# Atmega_128_Dev_Board.net
KiCad netlist of a schematic drawn in EAGLE
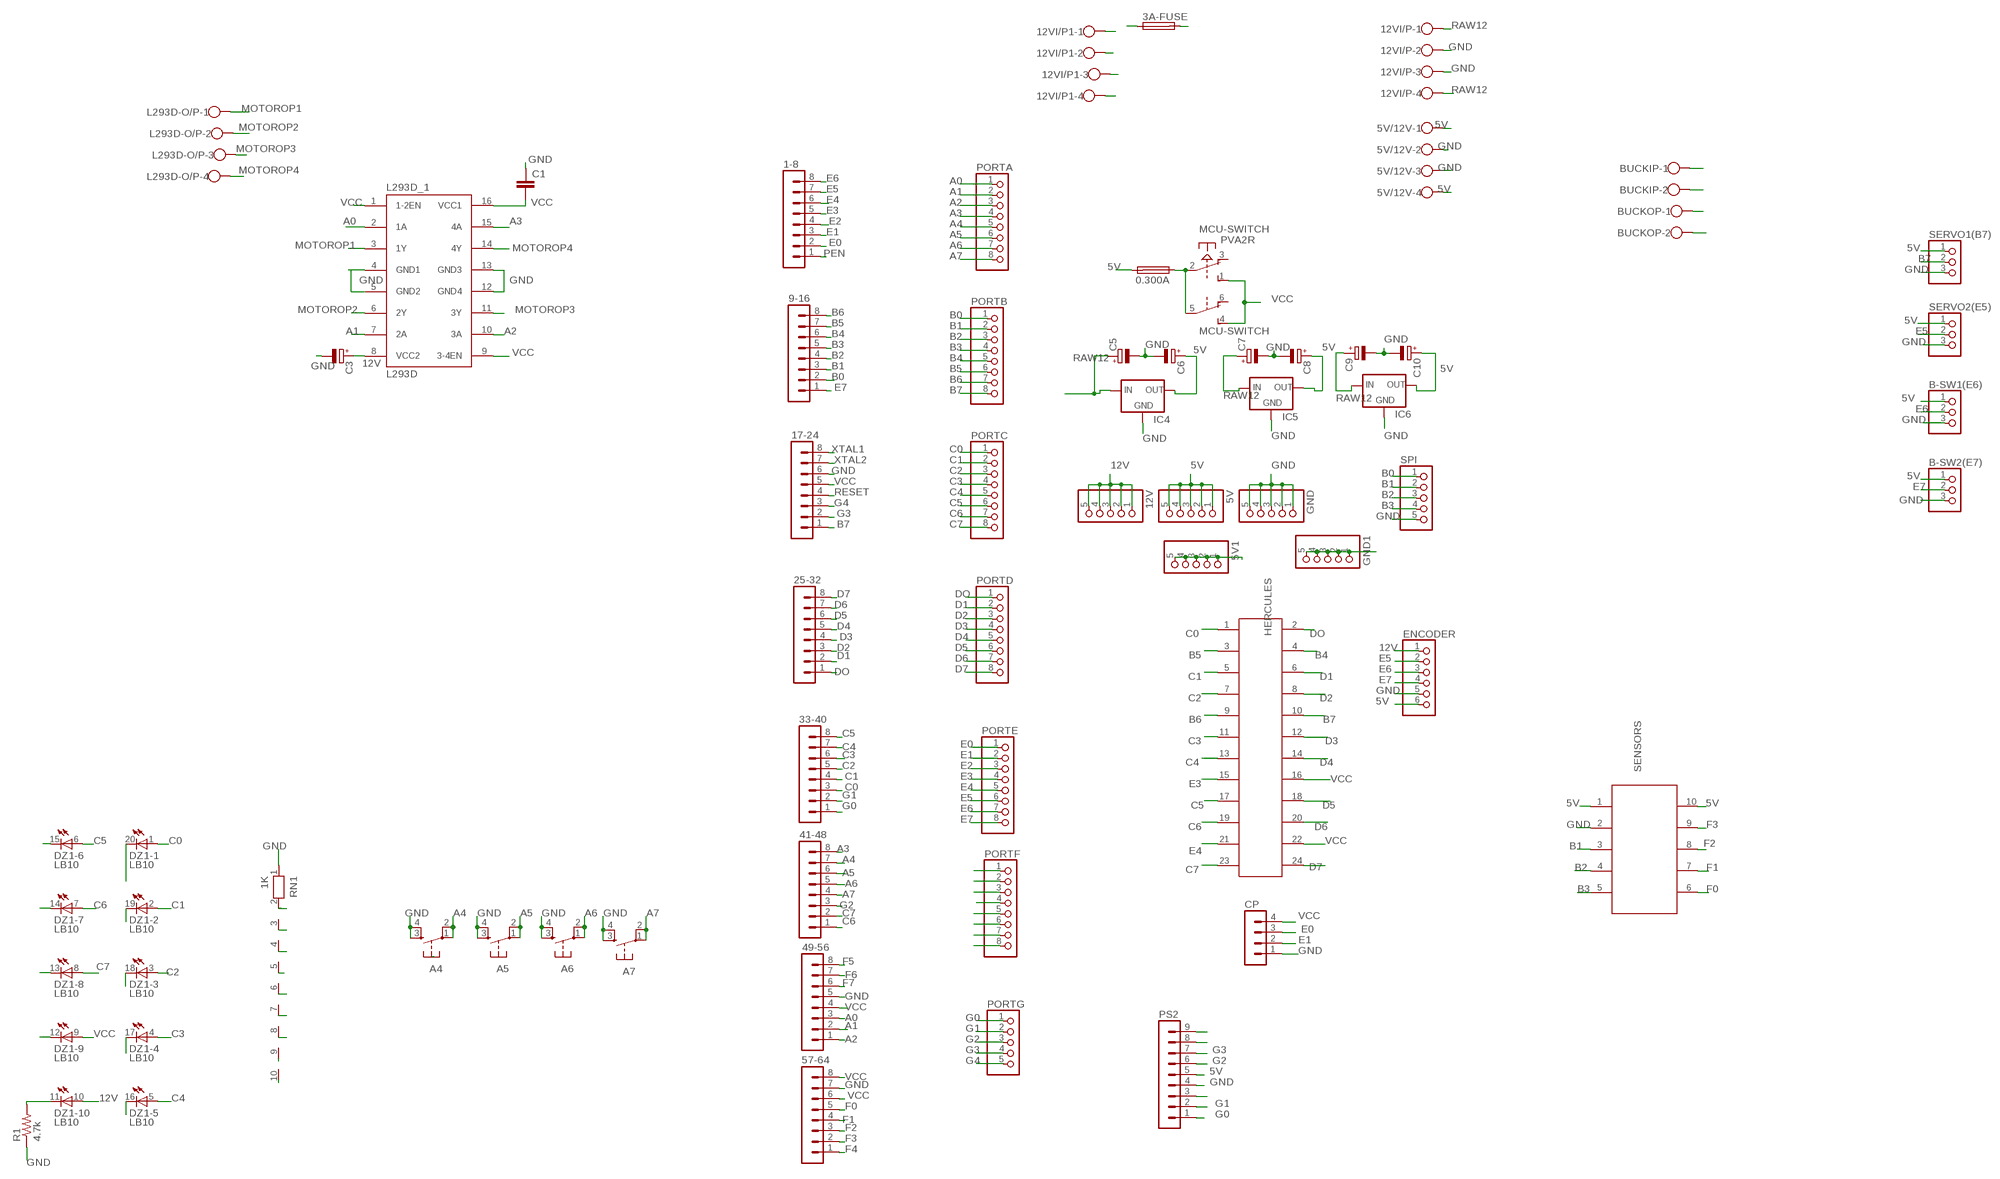
[diagram p0: schematic, sheet 1]

(export (version "E")
  (design (tool "Eeschema 10.0.6"))
  (components
    (comp (ref "0.300A")
      (value "SH25")
      (footprint "eagle-import:SH25")
      (fields (field (name "MF") "SCHURTER") (field (name "MPN") "0031.8211"))
      (libsource (lib "eagle-import") (part "SH25"))
    )
    (comp (ref "1-8")
      (value "MA08-1")
      (footprint "eagle-import:MA08-1")
      (libsource (lib "eagle-import") (part "MA08-1"))
    )
    (comp (ref "3A-FUSE")
      (value "SH25")
      (footprint "eagle-import:SH25")
      (fields (field (name "MF") "SCHURTER") (field (name "MPN") "0031.8211"))
      (libsource (lib "eagle-import") (part "SH25"))
    )
    (comp (ref "5V")
      (value "PINHD-1X5")
      (footprint "eagle-import:1X05")
      (libsource (lib "eagle-import") (part "PINHD-1X5"))
    )
    (comp (ref "5V/12V")
      (value "W237-4")
      (footprint "eagle-import:W237-4")
      (libsource (lib "eagle-import") (part "W237-4"))
    )
    (comp (ref "5V1")
      (value "PINHD-1X5")
      (footprint "eagle-import:1X05")
      (libsource (lib "eagle-import") (part "PINHD-1X5"))
    )
    (comp (ref "9-16")
      (value "MA08-1")
      (footprint "eagle-import:MA08-1")
      (libsource (lib "eagle-import") (part "MA08-1"))
    )
    (comp (ref "12V")
      (value "PINHD-1X5")
      (footprint "eagle-import:1X05")
      (libsource (lib "eagle-import") (part "PINHD-1X5"))
    )
    (comp (ref "12VI/P")
      (value "W237-4")
      (footprint "eagle-import:W237-4")
      (libsource (lib "eagle-import") (part "W237-4"))
    )
    (comp (ref "12VI/P1")
      (value "W237-4")
      (footprint "eagle-import:W237-4")
      (libsource (lib "eagle-import") (part "W237-4"))
    )
    (comp (ref "17-24")
      (value "MA08-1")
      (footprint "eagle-import:MA08-1")
      (libsource (lib "eagle-import") (part "MA08-1"))
    )
    (comp (ref "25-32")
      (value "MA08-1")
      (footprint "eagle-import:MA08-1")
      (libsource (lib "eagle-import") (part "MA08-1"))
    )
    (comp (ref "33-40")
      (value "MA08-1")
      (footprint "eagle-import:MA08-1")
      (libsource (lib "eagle-import") (part "MA08-1"))
    )
    (comp (ref "41-48")
      (value "MA08-1")
      (footprint "eagle-import:MA08-1")
      (libsource (lib "eagle-import") (part "MA08-1"))
    )
    (comp (ref "49-56")
      (value "MA08-1")
      (footprint "eagle-import:MA08-1")
      (libsource (lib "eagle-import") (part "MA08-1"))
    )
    (comp (ref "57-64")
      (value "MA08-1")
      (footprint "eagle-import:MA08-1")
      (libsource (lib "eagle-import") (part "MA08-1"))
    )
    (comp (ref "A4")
      (value "DTS-6")
      (footprint "eagle-import:DTS-6")
      (libsource (lib "eagle-import") (part "DTS-6"))
    )
    (comp (ref "A5")
      (value "DTS-6")
      (footprint "eagle-import:DTS-6")
      (libsource (lib "eagle-import") (part "DTS-6"))
    )
    (comp (ref "A6")
      (value "DTS-6")
      (footprint "eagle-import:DTS-6")
      (libsource (lib "eagle-import") (part "DTS-6"))
    )
    (comp (ref "A7")
      (value "DTS-6")
      (footprint "eagle-import:DTS-6")
      (libsource (lib "eagle-import") (part "DTS-6"))
    )
    (comp (ref "B-SW1(E6)")
      (value "PINHD-1X3")
      (footprint "eagle-import:1X03")
      (libsource (lib "eagle-import") (part "PINHD-1X3"))
    )
    (comp (ref "B-SW2(E7)")
      (value "PINHD-1X3")
      (footprint "eagle-import:1X03")
      (libsource (lib "eagle-import") (part "PINHD-1X3"))
    )
    (comp (ref "BUCKIP")
      (value "W237-102")
      (footprint "eagle-import:W237-102")
      (fields (field (name "MPN") "237-102"))
      (libsource (lib "eagle-import") (part "W237-102"))
    )
    (comp (ref "BUCKOP")
      (value "W237-102")
      (footprint "eagle-import:W237-102")
      (fields (field (name "MPN") "237-102"))
      (libsource (lib "eagle-import") (part "W237-102"))
    )
    (comp (ref "C1")
      (value "C5/2.5")
      (footprint "eagle-import:C5B2.5")
      (libsource (lib "eagle-import") (part "C5/2.5"))
    )
    (comp (ref "C3")
      (value "CPOL-EUE2.5-5")
      (footprint "eagle-import:E2,5-5")
      (libsource (lib "eagle-import") (part "CPOL-EUE2.5-5"))
    )
    (comp (ref "C5")
      (value "CPOL-EUE2.5-5")
      (footprint "eagle-import:E2,5-5")
      (libsource (lib "eagle-import") (part "CPOL-EUE2.5-5"))
    )
    (comp (ref "C6")
      (value "CPOL-EUE2.5-5")
      (footprint "eagle-import:E2,5-5")
      (libsource (lib "eagle-import") (part "CPOL-EUE2.5-5"))
    )
    (comp (ref "C7")
      (value "CPOL-EUE2.5-5")
      (footprint "eagle-import:E2,5-5")
      (libsource (lib "eagle-import") (part "CPOL-EUE2.5-5"))
    )
    (comp (ref "C8")
      (value "CPOL-EUE2.5-5")
      (footprint "eagle-import:E2,5-5")
      (libsource (lib "eagle-import") (part "CPOL-EUE2.5-5"))
    )
    (comp (ref "C9")
      (value "CPOL-EUE2.5-5")
      (footprint "eagle-import:E2,5-5")
      (libsource (lib "eagle-import") (part "CPOL-EUE2.5-5"))
    )
    (comp (ref "C10")
      (value "CPOL-EUE2.5-5")
      (footprint "eagle-import:E2,5-5")
      (libsource (lib "eagle-import") (part "CPOL-EUE2.5-5"))
    )
    (comp (ref "CP")
      (value "MA04-1")
      (footprint "eagle-import:MA04-1")
      (libsource (lib "eagle-import") (part "MA04-1"))
    )
    (comp (ref "DZ1")
      (value "LB10")
      (footprint "eagle-import:LB10")
      (libsource (lib "eagle-import") (part "LB10"))
    )
    (comp (ref "ENCODER")
      (value "PINHD-1X6")
      (footprint "eagle-import:1X06")
      (libsource (lib "eagle-import") (part "PINHD-1X6"))
    )
    (comp (ref "GND")
      (value "PINHD-1X5")
      (footprint "eagle-import:1X05")
      (libsource (lib "eagle-import") (part "PINHD-1X5"))
    )
    (comp (ref "GND1")
      (value "PINHD-1X5")
      (footprint "eagle-import:1X05")
      (libsource (lib "eagle-import") (part "PINHD-1X5"))
    )
    (comp (ref "HERCULES")
      (value "61202421621")
      (footprint "eagle-import:61202421621")
      (libsource (lib "eagle-import") (part "61202421621"))
    )
    (comp (ref "IC4")
      (value "78XXS")
      (footprint "eagle-import:78XXS")
      (libsource (lib "eagle-import") (part "78XXS"))
    )
    (comp (ref "IC5")
      (value "78XXS")
      (footprint "eagle-import:78XXS")
      (libsource (lib "eagle-import") (part "78XXS"))
    )
    (comp (ref "IC6")
      (value "78XXS")
      (footprint "eagle-import:78XXS")
      (libsource (lib "eagle-import") (part "78XXS"))
    )
    (comp (ref "L293D-O/P")
      (value "W237-4")
      (footprint "eagle-import:W237-4")
      (libsource (lib "eagle-import") (part "W237-4"))
    )
    (comp (ref "L293D_1")
      (value "L293D")
      (footprint "eagle-import:DIL16")
      (libsource (lib "eagle-import") (part "L293D"))
    )
    (comp (ref "MCU-SWITCH")
      (value "PVA2R")
      (footprint "eagle-import:PVA2R")
      (libsource (lib "eagle-import") (part "PVA2R"))
    )
    (comp (ref "PORTA")
      (value "PINHD-1X8")
      (footprint "eagle-import:1X08")
      (libsource (lib "eagle-import") (part "PINHD-1X8"))
    )
    (comp (ref "PORTB")
      (value "PINHD-1X8")
      (footprint "eagle-import:1X08")
      (libsource (lib "eagle-import") (part "PINHD-1X8"))
    )
    (comp (ref "PORTC")
      (value "PINHD-1X8")
      (footprint "eagle-import:1X08")
      (libsource (lib "eagle-import") (part "PINHD-1X8"))
    )
    (comp (ref "PORTD")
      (value "PINHD-1X8")
      (footprint "eagle-import:1X08")
      (libsource (lib "eagle-import") (part "PINHD-1X8"))
    )
    (comp (ref "PORTE")
      (value "PINHD-1X8")
      (footprint "eagle-import:1X08")
      (libsource (lib "eagle-import") (part "PINHD-1X8"))
    )
    (comp (ref "PORTF")
      (value "PINHD-1X8")
      (footprint "eagle-import:1X08")
      (libsource (lib "eagle-import") (part "PINHD-1X8"))
    )
    (comp (ref "PORTG")
      (value "PINHD-1X5")
      (footprint "eagle-import:1X05")
      (libsource (lib "eagle-import") (part "PINHD-1X5"))
    )
    (comp (ref "PS2")
      (value "MA09-1")
      (footprint "eagle-import:MA09-1")
      (libsource (lib "eagle-import") (part "MA09-1"))
    )
    (comp (ref "R1")
      (value "4.7k")
      (footprint "eagle-import:0204_7")
      (libsource (lib "eagle-import") (part "R-US_0204/7"))
    )
    (comp (ref "RN1")
      (value "1K")
      (footprint "eagle-import:RN-10")
      (libsource (lib "eagle-import") (part "RN09"))
    )
    (comp (ref "SENSORS")
      (value "66101021622")
      (footprint "eagle-import:66101021622")
      (libsource (lib "eagle-import") (part "66101021622"))
    )
    (comp (ref "SERVO1(B7)")
      (value "PINHD-1X3")
      (footprint "eagle-import:1X03")
      (libsource (lib "eagle-import") (part "PINHD-1X3"))
    )
    (comp (ref "SERVO2(E5)")
      (value "PINHD-1X3")
      (footprint "eagle-import:1X03")
      (libsource (lib "eagle-import") (part "PINHD-1X3"))
    )
    (comp (ref "SPI")
      (value "PINHD-1X5")
      (footprint "eagle-import:1X05")
      (libsource (lib "eagle-import") (part "PINHD-1X5"))
    )
  )
  (nets
    (net (code "1") (name "/2") (class "Default")
      (node (ref "DZ1") (pin "12") (pinfunction "C_12") (pintype "passive"))
      (node (ref "RN1") (pin "2") (pinfunction "2_2") (pintype "passive"))
    )
    (net (code "2") (name "/3") (class "Default")
      (node (ref "DZ1") (pin "13") (pinfunction "C_13") (pintype "passive"))
      (node (ref "RN1") (pin "3") (pinfunction "3_3") (pintype "passive"))
    )
    (net (code "3") (name "/4") (class "Default")
      (node (ref "DZ1") (pin "14") (pinfunction "C_14") (pintype "passive"))
      (node (ref "RN1") (pin "4") (pinfunction "4_4") (pintype "passive"))
    )
    (net (code "4") (name "/5") (class "Default")
      (node (ref "DZ1") (pin "15") (pinfunction "C_15") (pintype "passive"))
      (node (ref "RN1") (pin "5") (pinfunction "5_5") (pintype "passive"))
    )
    (net (code "5") (name "/5V") (class "Default")
      (node (ref "0.300A") (pin "2") (pinfunction "2_2") (pintype "passive"))
      (node (ref "5V") (pin "1") (pinfunction "1_1") (pintype "passive"))
      (node (ref "5V") (pin "2") (pinfunction "2_2") (pintype "passive"))
      (node (ref "5V") (pin "3") (pinfunction "3_3") (pintype "passive"))
      (node (ref "5V") (pin "4") (pinfunction "4_4") (pintype "passive"))
      (node (ref "5V") (pin "5") (pinfunction "5_5") (pintype "passive"))
      (node (ref "5V/12V") (pin "1") (pinfunction "KL_1") (pintype "passive"))
      (node (ref "5V/12V") (pin "4") (pinfunction "KL_4") (pintype "passive"))
      (node (ref "5V1") (pin "1") (pinfunction "1_1") (pintype "passive"))
      (node (ref "5V1") (pin "2") (pinfunction "2_2") (pintype "passive"))
      (node (ref "5V1") (pin "3") (pinfunction "3_3") (pintype "passive"))
      (node (ref "5V1") (pin "4") (pinfunction "4_4") (pintype "passive"))
      (node (ref "5V1") (pin "5") (pinfunction "5_5") (pintype "passive"))
      (node (ref "B-SW1(E6)") (pin "1") (pinfunction "1_1") (pintype "passive"))
      (node (ref "B-SW2(E7)") (pin "1") (pinfunction "1_1") (pintype "passive"))
      (node (ref "BUCKOP") (pin "2") (pinfunction "KL_2") (pintype "passive"))
      (node (ref "C10") (pin "+") (pinfunction "+_+") (pintype "passive"))
      (node (ref "C6") (pin "+") (pinfunction "+_+") (pintype "passive"))
      (node (ref "C8") (pin "+") (pinfunction "+_+") (pintype "passive"))
      (node (ref "ENCODER") (pin "6") (pinfunction "6_6") (pintype "passive"))
      (node (ref "IC4") (pin "OUT") (pinfunction "OUT_OUT") (pintype "passive"))
      (node (ref "IC5") (pin "OUT") (pinfunction "OUT_OUT") (pintype "passive"))
      (node (ref "IC6") (pin "OUT") (pinfunction "OUT_OUT") (pintype "passive"))
      (node (ref "PS2") (pin "5") (pinfunction "5_5") (pintype "passive"))
      (node (ref "SENSORS") (pin "1") (pinfunction "6_1") (pintype "bidirectional"))
      (node (ref "SENSORS") (pin "10") (pinfunction "1_10") (pintype "bidirectional"))
      (node (ref "SERVO1(B7)") (pin "1") (pinfunction "1_1") (pintype "passive"))
      (node (ref "SERVO2(E5)") (pin "1") (pinfunction "1_1") (pintype "passive"))
    )
    (net (code "6") (name "/6") (class "Default")
      (node (ref "DZ1") (pin "16") (pinfunction "C_16") (pintype "passive"))
      (node (ref "RN1") (pin "6") (pinfunction "6_6") (pintype "passive"))
    )
    (net (code "7") (name "/7") (class "Default")
      (node (ref "DZ1") (pin "17") (pinfunction "C_17") (pintype "passive"))
      (node (ref "RN1") (pin "7") (pinfunction "7_7") (pintype "passive"))
    )
    (net (code "8") (name "/8") (class "Default")
      (node (ref "DZ1") (pin "18") (pinfunction "C_18") (pintype "passive"))
      (node (ref "RN1") (pin "8") (pinfunction "8_8") (pintype "passive"))
    )
    (net (code "9") (name "/9") (class "Default")
      (node (ref "DZ1") (pin "19") (pinfunction "C_19") (pintype "passive"))
      (node (ref "RN1") (pin "9") (pinfunction "9_9") (pintype "passive"))
    )
    (net (code "10") (name "/10") (class "Default")
      (node (ref "DZ1") (pin "20") (pinfunction "C_20") (pintype "passive"))
      (node (ref "RN1") (pin "10") (pinfunction "10_10") (pintype "passive"))
    )
    (net (code "11") (name "/12V") (class "Default")
      (node (ref "12V") (pin "1") (pinfunction "1_1") (pintype "passive"))
      (node (ref "12V") (pin "2") (pinfunction "2_2") (pintype "passive"))
      (node (ref "12V") (pin "3") (pinfunction "3_3") (pintype "passive"))
      (node (ref "12V") (pin "4") (pinfunction "4_4") (pintype "passive"))
      (node (ref "12V") (pin "5") (pinfunction "5_5") (pintype "passive"))
      (node (ref "3A-FUSE") (pin "2") (pinfunction "2_2") (pintype "passive"))
      (node (ref "C3") (pin "+") (pinfunction "+_+") (pintype "passive"))
      (node (ref "DZ1") (pin "10") (pinfunction "A_10") (pintype "passive"))
      (node (ref "ENCODER") (pin "1") (pinfunction "1_1") (pintype "passive"))
      (node (ref "L293D_1") (pin "8") (pinfunction "VCC2_8") (pintype "power_in"))
    )
    (net (code "12") (name "/A0") (class "Default")
      (node (ref "49-56") (pin "3") (pinfunction "3_3") (pintype "passive"))
      (node (ref "L293D_1") (pin "2") (pinfunction "1A_2") (pintype "input"))
      (node (ref "PORTA") (pin "1") (pinfunction "1_1") (pintype "passive"))
    )
    (net (code "13") (name "/A1") (class "Default")
      (node (ref "49-56") (pin "2") (pinfunction "2_2") (pintype "passive"))
      (node (ref "L293D_1") (pin "7") (pinfunction "2A_7") (pintype "input"))
      (node (ref "PORTA") (pin "2") (pinfunction "2_2") (pintype "passive"))
    )
    (net (code "14") (name "/A2") (class "Default")
      (node (ref "49-56") (pin "1") (pinfunction "1_1") (pintype "passive"))
      (node (ref "L293D_1") (pin "10") (pinfunction "3A_10") (pintype "input"))
      (node (ref "PORTA") (pin "3") (pinfunction "3_3") (pintype "passive"))
    )
    (net (code "15") (name "/A3") (class "Default")
      (node (ref "41-48") (pin "8") (pinfunction "8_8") (pintype "passive"))
      (node (ref "L293D_1") (pin "15") (pinfunction "4A_15") (pintype "input"))
      (node (ref "PORTA") (pin "4") (pinfunction "4_4") (pintype "passive"))
    )
    (net (code "16") (name "/A4") (class "Default")
      (node (ref "41-48") (pin "7") (pinfunction "7_7") (pintype "passive"))
      (node (ref "A4") (pin "1") (pinfunction "1_1") (pintype "passive"))
      (node (ref "A4") (pin "2") (pinfunction "2_2") (pintype "passive"))
      (node (ref "PORTA") (pin "5") (pinfunction "5_5") (pintype "passive"))
    )
    (net (code "17") (name "/A5") (class "Default")
      (node (ref "41-48") (pin "6") (pinfunction "6_6") (pintype "passive"))
      (node (ref "A5") (pin "1") (pinfunction "1_1") (pintype "passive"))
      (node (ref "A5") (pin "2") (pinfunction "2_2") (pintype "passive"))
      (node (ref "PORTA") (pin "6") (pinfunction "6_6") (pintype "passive"))
    )
    (net (code "18") (name "/A6") (class "Default")
      (node (ref "41-48") (pin "5") (pinfunction "5_5") (pintype "passive"))
      (node (ref "A6") (pin "1") (pinfunction "1_1") (pintype "passive"))
      (node (ref "A6") (pin "2") (pinfunction "2_2") (pintype "passive"))
      (node (ref "PORTA") (pin "7") (pinfunction "7_7") (pintype "passive"))
    )
    (net (code "19") (name "/A7") (class "Default")
      (node (ref "41-48") (pin "4") (pinfunction "4_4") (pintype "passive"))
      (node (ref "A7") (pin "1") (pinfunction "1_1") (pintype "passive"))
      (node (ref "A7") (pin "2") (pinfunction "2_2") (pintype "passive"))
      (node (ref "PORTA") (pin "8") (pinfunction "8_8") (pintype "passive"))
    )
    (net (code "20") (name "/B0") (class "Default")
      (node (ref "9-16") (pin "2") (pinfunction "2_2") (pintype "passive"))
      (node (ref "PORTB") (pin "1") (pinfunction "1_1") (pintype "passive"))
      (node (ref "SPI") (pin "1") (pinfunction "1_1") (pintype "passive"))
    )
    (net (code "21") (name "/B1") (class "Default")
      (node (ref "9-16") (pin "3") (pinfunction "3_3") (pintype "passive"))
      (node (ref "PORTB") (pin "2") (pinfunction "2_2") (pintype "passive"))
      (node (ref "SENSORS") (pin "3") (pinfunction "8_3") (pintype "bidirectional"))
      (node (ref "SPI") (pin "2") (pinfunction "2_2") (pintype "passive"))
    )
    (net (code "22") (name "/B2") (class "Default")
      (node (ref "9-16") (pin "4") (pinfunction "4_4") (pintype "passive"))
      (node (ref "PORTB") (pin "3") (pinfunction "3_3") (pintype "passive"))
      (node (ref "SENSORS") (pin "4") (pinfunction "9_4") (pintype "bidirectional"))
      (node (ref "SPI") (pin "3") (pinfunction "3_3") (pintype "passive"))
    )
    (net (code "23") (name "/B3") (class "Default")
      (node (ref "9-16") (pin "5") (pinfunction "5_5") (pintype "passive"))
      (node (ref "PORTB") (pin "4") (pinfunction "4_4") (pintype "passive"))
      (node (ref "SENSORS") (pin "5") (pinfunction "10_5") (pintype "bidirectional"))
      (node (ref "SPI") (pin "4") (pinfunction "4_4") (pintype "passive"))
    )
    (net (code "24") (name "/B4") (class "Default")
      (node (ref "9-16") (pin "6") (pinfunction "6_6") (pintype "passive"))
      (node (ref "HERCULES") (pin "4") (pinfunction "4_4") (pintype "passive"))
      (node (ref "PORTB") (pin "5") (pinfunction "5_5") (pintype "passive"))
    )
    (net (code "25") (name "/B5") (class "Default")
      (node (ref "9-16") (pin "7") (pinfunction "7_7") (pintype "passive"))
      (node (ref "HERCULES") (pin "3") (pinfunction "3_3") (pintype "passive"))
      (node (ref "PORTB") (pin "6") (pinfunction "6_6") (pintype "passive"))
    )
    (net (code "26") (name "/B6") (class "Default")
      (node (ref "9-16") (pin "8") (pinfunction "8_8") (pintype "passive"))
      (node (ref "HERCULES") (pin "9") (pinfunction "9_9") (pintype "passive"))
      (node (ref "PORTB") (pin "7") (pinfunction "7_7") (pintype "passive"))
    )
    (net (code "27") (name "/B7") (class "Default")
      (node (ref "17-24") (pin "1") (pinfunction "1_1") (pintype "passive"))
      (node (ref "HERCULES") (pin "10") (pinfunction "10_10") (pintype "passive"))
      (node (ref "PORTB") (pin "8") (pinfunction "8_8") (pintype "passive"))
      (node (ref "SERVO1(B7)") (pin "2") (pinfunction "2_2") (pintype "passive"))
    )
    (net (code "28") (name "/C0") (class "Default")
      (node (ref "33-40") (pin "3") (pinfunction "3_3") (pintype "passive"))
      (node (ref "DZ1") (pin "1") (pinfunction "A_1") (pintype "passive"))
      (node (ref "HERCULES") (pin "1") (pinfunction "1_1") (pintype "passive"))
      (node (ref "PORTC") (pin "1") (pinfunction "1_1") (pintype "passive"))
    )
    (net (code "29") (name "/C1") (class "Default")
      (node (ref "33-40") (pin "4") (pinfunction "4_4") (pintype "passive"))
      (node (ref "DZ1") (pin "2") (pinfunction "A_2") (pintype "passive"))
      (node (ref "HERCULES") (pin "5") (pinfunction "5_5") (pintype "passive"))
      (node (ref "PORTC") (pin "2") (pinfunction "2_2") (pintype "passive"))
    )
    (net (code "30") (name "/C2") (class "Default")
      (node (ref "33-40") (pin "5") (pinfunction "5_5") (pintype "passive"))
      (node (ref "DZ1") (pin "3") (pinfunction "A_3") (pintype "passive"))
      (node (ref "HERCULES") (pin "7") (pinfunction "7_7") (pintype "passive"))
      (node (ref "PORTC") (pin "3") (pinfunction "3_3") (pintype "passive"))
    )
    (net (code "31") (name "/C3") (class "Default")
      (node (ref "33-40") (pin "6") (pinfunction "6_6") (pintype "passive"))
      (node (ref "DZ1") (pin "4") (pinfunction "A_4") (pintype "passive"))
      (node (ref "HERCULES") (pin "11") (pinfunction "11_11") (pintype "passive"))
      (node (ref "PORTC") (pin "4") (pinfunction "4_4") (pintype "passive"))
    )
    (net (code "32") (name "/C4") (class "Default")
      (node (ref "33-40") (pin "7") (pinfunction "7_7") (pintype "passive"))
      (node (ref "DZ1") (pin "5") (pinfunction "A_5") (pintype "passive"))
      (node (ref "HERCULES") (pin "13") (pinfunction "13_13") (pintype "passive"))
      (node (ref "PORTC") (pin "5") (pinfunction "5_5") (pintype "passive"))
    )
    (net (code "33") (name "/C5") (class "Default")
      (node (ref "33-40") (pin "8") (pinfunction "8_8") (pintype "passive"))
      (node (ref "DZ1") (pin "6") (pinfunction "A_6") (pintype "passive"))
      (node (ref "HERCULES") (pin "17") (pinfunction "17_17") (pintype "passive"))
      (node (ref "PORTC") (pin "6") (pinfunction "6_6") (pintype "passive"))
    )
    (net (code "34") (name "/C6") (class "Default")
      (node (ref "41-48") (pin "1") (pinfunction "1_1") (pintype "passive"))
      (node (ref "DZ1") (pin "7") (pinfunction "A_7") (pintype "passive"))
      (node (ref "HERCULES") (pin "19") (pinfunction "19_19") (pintype "passive"))
      (node (ref "PORTC") (pin "7") (pinfunction "7_7") (pintype "passive"))
    )
    (net (code "35") (name "/C7") (class "Default")
      (node (ref "41-48") (pin "2") (pinfunction "2_2") (pintype "passive"))
      (node (ref "DZ1") (pin "8") (pinfunction "A_8") (pintype "passive"))
      (node (ref "HERCULES") (pin "23") (pinfunction "23_23") (pintype "passive"))
      (node (ref "PORTC") (pin "8") (pinfunction "8_8") (pintype "passive"))
    )
    (net (code "36") (name "/D1") (class "Default")
      (node (ref "25-32") (pin "2") (pinfunction "2_2") (pintype "passive"))
      (node (ref "HERCULES") (pin "6") (pinfunction "6_6") (pintype "passive"))
      (node (ref "PORTD") (pin "2") (pinfunction "2_2") (pintype "passive"))
    )
    (net (code "37") (name "/D2") (class "Default")
      (node (ref "25-32") (pin "3") (pinfunction "3_3") (pintype "passive"))
      (node (ref "HERCULES") (pin "8") (pinfunction "8_8") (pintype "passive"))
      (node (ref "PORTD") (pin "3") (pinfunction "3_3") (pintype "passive"))
    )
    (net (code "38") (name "/D3") (class "Default")
      (node (ref "25-32") (pin "4") (pinfunction "4_4") (pintype "passive"))
      (node (ref "HERCULES") (pin "12") (pinfunction "12_12") (pintype "passive"))
      (node (ref "PORTD") (pin "4") (pinfunction "4_4") (pintype "passive"))
    )
    (net (code "39") (name "/D4") (class "Default")
      (node (ref "25-32") (pin "5") (pinfunction "5_5") (pintype "passive"))
      (node (ref "HERCULES") (pin "14") (pinfunction "14_14") (pintype "passive"))
      (node (ref "PORTD") (pin "5") (pinfunction "5_5") (pintype "passive"))
    )
    (net (code "40") (name "/D5") (class "Default")
      (node (ref "25-32") (pin "6") (pinfunction "6_6") (pintype "passive"))
      (node (ref "HERCULES") (pin "18") (pinfunction "18_18") (pintype "passive"))
      (node (ref "PORTD") (pin "6") (pinfunction "6_6") (pintype "passive"))
    )
    (net (code "41") (name "/D6") (class "Default")
      (node (ref "25-32") (pin "7") (pinfunction "7_7") (pintype "passive"))
      (node (ref "HERCULES") (pin "20") (pinfunction "20_20") (pintype "passive"))
      (node (ref "PORTD") (pin "7") (pinfunction "7_7") (pintype "passive"))
    )
    (net (code "42") (name "/D7") (class "Default")
      (node (ref "25-32") (pin "8") (pinfunction "8_8") (pintype "passive"))
      (node (ref "HERCULES") (pin "24") (pinfunction "24_24") (pintype "passive"))
      (node (ref "PORTD") (pin "8") (pinfunction "8_8") (pintype "passive"))
    )
    (net (code "43") (name "/DO") (class "Default")
      (node (ref "25-32") (pin "1") (pinfunction "1_1") (pintype "passive"))
      (node (ref "HERCULES") (pin "2") (pinfunction "2_2") (pintype "passive"))
      (node (ref "PORTD") (pin "1") (pinfunction "1_1") (pintype "passive"))
    )
    (net (code "44") (name "/E0") (class "Default")
      (node (ref "1-8") (pin "2") (pinfunction "2_2") (pintype "passive"))
      (node (ref "CP") (pin "3") (pinfunction "3_3") (pintype "passive"))
      (node (ref "PORTE") (pin "1") (pinfunction "1_1") (pintype "passive"))
    )
    (net (code "45") (name "/E1") (class "Default")
      (node (ref "1-8") (pin "3") (pinfunction "3_3") (pintype "passive"))
      (node (ref "CP") (pin "2") (pinfunction "2_2") (pintype "passive"))
      (node (ref "PORTE") (pin "2") (pinfunction "2_2") (pintype "passive"))
    )
    (net (code "46") (name "/E2") (class "Default")
      (node (ref "1-8") (pin "4") (pinfunction "4_4") (pintype "passive"))
      (node (ref "PORTE") (pin "3") (pinfunction "3_3") (pintype "passive"))
    )
    (net (code "47") (name "/E3") (class "Default")
      (node (ref "1-8") (pin "5") (pinfunction "5_5") (pintype "passive"))
      (node (ref "HERCULES") (pin "15") (pinfunction "15_15") (pintype "passive"))
      (node (ref "PORTE") (pin "4") (pinfunction "4_4") (pintype "passive"))
    )
    (net (code "48") (name "/E4") (class "Default")
      (node (ref "1-8") (pin "6") (pinfunction "6_6") (pintype "passive"))
      (node (ref "HERCULES") (pin "21") (pinfunction "21_21") (pintype "passive"))
      (node (ref "PORTE") (pin "5") (pinfunction "5_5") (pintype "passive"))
    )
    (net (code "49") (name "/E5") (class "Default")
      (node (ref "1-8") (pin "7") (pinfunction "7_7") (pintype "passive"))
      (node (ref "ENCODER") (pin "2") (pinfunction "2_2") (pintype "passive"))
      (node (ref "PORTE") (pin "6") (pinfunction "6_6") (pintype "passive"))
      (node (ref "SERVO2(E5)") (pin "2") (pinfunction "2_2") (pintype "passive"))
    )
    (net (code "50") (name "/E6") (class "Default")
      (node (ref "1-8") (pin "8") (pinfunction "8_8") (pintype "passive"))
      (node (ref "B-SW1(E6)") (pin "2") (pinfunction "2_2") (pintype "passive"))
      (node (ref "ENCODER") (pin "3") (pinfunction "3_3") (pintype "passive"))
      (node (ref "PORTE") (pin "7") (pinfunction "7_7") (pintype "passive"))
    )
    (net (code "51") (name "/E7") (class "Default")
      (node (ref "9-16") (pin "1") (pinfunction "1_1") (pintype "passive"))
      (node (ref "B-SW2(E7)") (pin "2") (pinfunction "2_2") (pintype "passive"))
      (node (ref "ENCODER") (pin "4") (pinfunction "4_4") (pintype "passive"))
      (node (ref "PORTE") (pin "8") (pinfunction "8_8") (pintype "passive"))
    )
    (net (code "52") (name "/F0") (class "Default")
      (node (ref "57-64") (pin "5") (pinfunction "5_5") (pintype "passive"))
      (node (ref "PORTF") (pin "1") (pinfunction "1_1") (pintype "passive"))
      (node (ref "SENSORS") (pin "6") (pinfunction "5_6") (pintype "bidirectional"))
    )
    (net (code "53") (name "/F1") (class "Default")
      (node (ref "57-64") (pin "4") (pinfunction "4_4") (pintype "passive"))
      (node (ref "PORTF") (pin "2") (pinfunction "2_2") (pintype "passive"))
      (node (ref "SENSORS") (pin "7") (pinfunction "4_7") (pintype "bidirectional"))
    )
    (net (code "54") (name "/F2") (class "Default")
      (node (ref "57-64") (pin "3") (pinfunction "3_3") (pintype "passive"))
      (node (ref "PORTF") (pin "3") (pinfunction "3_3") (pintype "passive"))
      (node (ref "SENSORS") (pin "8") (pinfunction "3_8") (pintype "bidirectional"))
    )
    (net (code "55") (name "/F3") (class "Default")
      (node (ref "57-64") (pin "2") (pinfunction "2_2") (pintype "passive"))
      (node (ref "PORTF") (pin "4") (pinfunction "4_4") (pintype "passive"))
      (node (ref "SENSORS") (pin "9") (pinfunction "2_9") (pintype "bidirectional"))
    )
    (net (code "56") (name "/F4") (class "Default")
      (node (ref "57-64") (pin "1") (pinfunction "1_1") (pintype "passive"))
      (node (ref "PORTF") (pin "5") (pinfunction "5_5") (pintype "passive"))
    )
    (net (code "57") (name "/F5") (class "Default")
      (node (ref "49-56") (pin "8") (pinfunction "8_8") (pintype "passive"))
      (node (ref "PORTF") (pin "6") (pinfunction "6_6") (pintype "passive"))
    )
    (net (code "58") (name "/F6") (class "Default")
      (node (ref "49-56") (pin "7") (pinfunction "7_7") (pintype "passive"))
      (node (ref "PORTF") (pin "7") (pinfunction "7_7") (pintype "passive"))
    )
    (net (code "59") (name "/F7") (class "Default")
      (node (ref "49-56") (pin "6") (pinfunction "6_6") (pintype "passive"))
      (node (ref "PORTF") (pin "8") (pinfunction "8_8") (pintype "passive"))
    )
    (net (code "60") (name "/G0") (class "Default")
      (node (ref "33-40") (pin "1") (pinfunction "1_1") (pintype "passive"))
      (node (ref "PORTG") (pin "1") (pinfunction "1_1") (pintype "passive"))
      (node (ref "PS2") (pin "1") (pinfunction "1_1") (pintype "passive"))
    )
    (net (code "61") (name "/G1") (class "Default")
      (node (ref "33-40") (pin "2") (pinfunction "2_2") (pintype "passive"))
      (node (ref "PORTG") (pin "2") (pinfunction "2_2") (pintype "passive"))
      (node (ref "PS2") (pin "2") (pinfunction "2_2") (pintype "passive"))
    )
    (net (code "62") (name "/G2") (class "Default")
      (node (ref "41-48") (pin "3") (pinfunction "3_3") (pintype "passive"))
      (node (ref "PORTG") (pin "3") (pinfunction "3_3") (pintype "passive"))
      (node (ref "PS2") (pin "6") (pinfunction "6_6") (pintype "passive"))
    )
    (net (code "63") (name "/G3") (class "Default")
      (node (ref "17-24") (pin "2") (pinfunction "2_2") (pintype "passive"))
      (node (ref "PORTG") (pin "4") (pinfunction "4_4") (pintype "passive"))
      (node (ref "PS2") (pin "7") (pinfunction "7_7") (pintype "passive"))
    )
    (net (code "64") (name "/G4") (class "Default")
      (node (ref "17-24") (pin "3") (pinfunction "3_3") (pintype "passive"))
      (node (ref "PORTG") (pin "5") (pinfunction "5_5") (pintype "passive"))
    )
    (net (code "65") (name "/GND") (class "Default")
      (node (ref "12VI/P") (pin "2") (pinfunction "KL_2") (pintype "passive"))
      (node (ref "12VI/P") (pin "3") (pinfunction "KL_3") (pintype "passive"))
      (node (ref "12VI/P1") (pin "2") (pinfunction "KL_2") (pintype "passive"))
      (node (ref "12VI/P1") (pin "3") (pinfunction "KL_3") (pintype "passive"))
      (node (ref "17-24") (pin "6") (pinfunction "6_6") (pintype "passive"))
      (node (ref "49-56") (pin "5") (pinfunction "5_5") (pintype "passive"))
      (node (ref "57-64") (pin "7") (pinfunction "7_7") (pintype "passive"))
      (node (ref "5V/12V") (pin "2") (pinfunction "KL_2") (pintype "passive"))
      (node (ref "5V/12V") (pin "3") (pinfunction "KL_3") (pintype "passive"))
      (node (ref "A4") (pin "3") (pinfunction "3_3") (pintype "passive"))
      (node (ref "A4") (pin "4") (pinfunction "4_4") (pintype "passive"))
      (node (ref "A5") (pin "3") (pinfunction "3_3") (pintype "passive"))
      (node (ref "A5") (pin "4") (pinfunction "4_4") (pintype "passive"))
      (node (ref "A6") (pin "3") (pinfunction "3_3") (pintype "passive"))
      (node (ref "A6") (pin "4") (pinfunction "4_4") (pintype "passive"))
      (node (ref "A7") (pin "3") (pinfunction "3_3") (pintype "passive"))
      (node (ref "A7") (pin "4") (pinfunction "4_4") (pintype "passive"))
      (node (ref "B-SW1(E6)") (pin "3") (pinfunction "3_3") (pintype "passive"))
      (node (ref "B-SW2(E7)") (pin "3") (pinfunction "3_3") (pintype "passive"))
      (node (ref "BUCKIP") (pin "2") (pinfunction "KL_2") (pintype "passive"))
      (node (ref "BUCKOP") (pin "1") (pinfunction "KL_1") (pintype "passive"))
      (node (ref "C1") (pin "1") (pinfunction "1_1") (pintype "passive"))
      (node (ref "C10") (pin "-") (pinfunction "-_-") (pintype "passive"))
      (node (ref "C3") (pin "-") (pinfunction "-_-") (pintype "passive"))
      (node (ref "C5") (pin "-") (pinfunction "-_-") (pintype "passive"))
      (node (ref "C6") (pin "-") (pinfunction "-_-") (pintype "passive"))
      (node (ref "C7") (pin "-") (pinfunction "-_-") (pintype "passive"))
      (node (ref "C8") (pin "-") (pinfunction "-_-") (pintype "passive"))
      (node (ref "C9") (pin "-") (pinfunction "-_-") (pintype "passive"))
      (node (ref "CP") (pin "1") (pinfunction "1_1") (pintype "passive"))
      (node (ref "ENCODER") (pin "5") (pinfunction "5_5") (pintype "passive"))
      (node (ref "GND") (pin "1") (pinfunction "1_1") (pintype "passive"))
      (node (ref "GND") (pin "2") (pinfunction "2_2") (pintype "passive"))
      (node (ref "GND") (pin "3") (pinfunction "3_3") (pintype "passive"))
      (node (ref "GND") (pin "4") (pinfunction "4_4") (pintype "passive"))
      (node (ref "GND") (pin "5") (pinfunction "5_5") (pintype "passive"))
      (node (ref "GND1") (pin "1") (pinfunction "1_1") (pintype "passive"))
      (node (ref "GND1") (pin "2") (pinfunction "2_2") (pintype "passive"))
      (node (ref "GND1") (pin "3") (pinfunction "3_3") (pintype "passive"))
      (node (ref "GND1") (pin "4") (pinfunction "4_4") (pintype "passive"))
      (node (ref "GND1") (pin "5") (pinfunction "5_5") (pintype "passive"))
      (node (ref "IC4") (pin "GND") (pinfunction "GND_GND") (pintype "input"))
      (node (ref "IC5") (pin "GND") (pinfunction "GND_GND") (pintype "input"))
      (node (ref "IC6") (pin "GND") (pinfunction "GND_GND") (pintype "input"))
      (node (ref "L293D_1") (pin "12") (pinfunction "GND4_12") (pintype "power_in"))
      (node (ref "L293D_1") (pin "13") (pinfunction "GND3_13") (pintype "power_in"))
      (node (ref "L293D_1") (pin "4") (pinfunction "GND1_4") (pintype "power_in"))
      (node (ref "L293D_1") (pin "5") (pinfunction "GND2_5") (pintype "power_in"))
      (node (ref "PS2") (pin "4") (pinfunction "4_4") (pintype "passive"))
      (node (ref "R1") (pin "1") (pinfunction "1_1") (pintype "passive"))
      (node (ref "RN1") (pin "1") (pinfunction "1_1") (pintype "passive"))
      (node (ref "SENSORS") (pin "2") (pinfunction "7_2") (pintype "bidirectional"))
      (node (ref "SERVO1(B7)") (pin "3") (pinfunction "3_3") (pintype "passive"))
      (node (ref "SERVO2(E5)") (pin "3") (pinfunction "3_3") (pintype "passive"))
      (node (ref "SPI") (pin "5") (pinfunction "5_5") (pintype "passive"))
    )
    (net (code "66") (name "/MOTOROP1") (class "Default")
      (node (ref "L293D-O/P") (pin "1") (pinfunction "KL_1") (pintype "passive"))
      (node (ref "L293D_1") (pin "3") (pinfunction "1Y_3") (pintype "output"))
    )
    (net (code "67") (name "/MOTOROP2") (class "Default")
      (node (ref "L293D-O/P") (pin "2") (pinfunction "KL_2") (pintype "passive"))
      (node (ref "L293D_1") (pin "6") (pinfunction "2Y_6") (pintype "output"))
    )
    (net (code "68") (name "/MOTOROP3") (class "Default")
      (node (ref "L293D-O/P") (pin "3") (pinfunction "KL_3") (pintype "passive"))
      (node (ref "L293D_1") (pin "11") (pinfunction "3Y_11") (pintype "output"))
    )
    (net (code "69") (name "/MOTOROP4") (class "Default")
      (node (ref "L293D-O/P") (pin "4") (pinfunction "KL_4") (pintype "passive"))
      (node (ref "L293D_1") (pin "14") (pinfunction "4Y_14") (pintype "output"))
    )
    (net (code "70") (name "/PEN") (class "Default")
      (node (ref "1-8") (pin "1") (pinfunction "1_1") (pintype "passive"))
    )
    (net (code "71") (name "/RAW12") (class "Default")
      (node (ref "12VI/P") (pin "1") (pinfunction "KL_1") (pintype "passive"))
      (node (ref "12VI/P") (pin "4") (pinfunction "KL_4") (pintype "passive"))
      (node (ref "12VI/P1") (pin "1") (pinfunction "KL_1") (pintype "passive"))
      (node (ref "12VI/P1") (pin "4") (pinfunction "KL_4") (pintype "passive"))
      (node (ref "3A-FUSE") (pin "1") (pinfunction "1_1") (pintype "passive"))
      (node (ref "BUCKIP") (pin "1") (pinfunction "KL_1") (pintype "passive"))
      (node (ref "C5") (pin "+") (pinfunction "+_+") (pintype "passive"))
      (node (ref "C7") (pin "+") (pinfunction "+_+") (pintype "passive"))
      (node (ref "C9") (pin "+") (pinfunction "+_+") (pintype "passive"))
      (node (ref "IC4") (pin "IN") (pinfunction "IN_IN") (pintype "input"))
      (node (ref "IC5") (pin "IN") (pinfunction "IN_IN") (pintype "input"))
      (node (ref "IC6") (pin "IN") (pinfunction "IN_IN") (pintype "input"))
    )
    (net (code "72") (name "/RESET") (class "Default")
      (node (ref "17-24") (pin "4") (pinfunction "4_4") (pintype "passive"))
    )
    (net (code "73") (name "/VCC") (class "Default")
      (node (ref "17-24") (pin "5") (pinfunction "5_5") (pintype "passive"))
      (node (ref "49-56") (pin "4") (pinfunction "4_4") (pintype "passive"))
      (node (ref "57-64") (pin "6") (pinfunction "6_6") (pintype "passive"))
      (node (ref "57-64") (pin "8") (pinfunction "8_8") (pintype "passive"))
      (node (ref "C1") (pin "2") (pinfunction "2_2") (pintype "passive"))
      (node (ref "CP") (pin "4") (pinfunction "4_4") (pintype "passive"))
      (node (ref "DZ1") (pin "9") (pinfunction "A_9") (pintype "passive"))
      (node (ref "HERCULES") (pin "16") (pinfunction "16_16") (pintype "passive"))
      (node (ref "HERCULES") (pin "22") (pinfunction "22_22") (pintype "passive"))
      (node (ref "L293D_1") (pin "1") (pinfunction "1-2EN_1") (pintype "input"))
      (node (ref "L293D_1") (pin "16") (pinfunction "VCC1_16") (pintype "power_in"))
      (node (ref "L293D_1") (pin "9") (pinfunction "3-4EN_9") (pintype "input"))
      (node (ref "MCU-SWITCH") (pin "1") (pinfunction "S_1") (pintype "passive"))
      (node (ref "MCU-SWITCH") (pin "4") (pinfunction "S_4") (pintype "passive"))
    )
    (net (code "74") (name "/XTAL1") (class "Default")
      (node (ref "17-24") (pin "8") (pinfunction "8_8") (pintype "passive"))
    )
    (net (code "75") (name "/XTAL2") (class "Default")
      (node (ref "17-24") (pin "7") (pinfunction "7_7") (pintype "passive"))
    )
    (net (code "76") (name "Net-(DZ1B-C)") (class "Default")
      (node (ref "DZ1") (pin "11") (pinfunction "C_11") (pintype "passive"))
      (node (ref "R1") (pin "2") (pinfunction "2_2") (pintype "passive"))
    )
    (net (code "77") (name "Net-(MCU-SWITCHA-P)") (class "Default")
      (node (ref "0.300A") (pin "1") (pinfunction "1_1") (pintype "passive"))
      (node (ref "MCU-SWITCH") (pin "2") (pinfunction "P_2") (pintype "passive"))
      (node (ref "MCU-SWITCH") (pin "5") (pinfunction "P_5") (pintype "passive"))
    )
    (net (code "78") (name "unconnected-(MCU-SWITCHA-O-Pad3)") (class "Default")
      (node (ref "MCU-SWITCH") (pin "3") (pinfunction "O_3") (pintype "passive"))
    )
    (net (code "79") (name "unconnected-(MCU-SWITCHB-O-Pad6)") (class "Default")
      (node (ref "MCU-SWITCH") (pin "6") (pinfunction "O_6") (pintype "passive"))
    )
    (net (code "80") (name "unconnected-(PS2-Pad3)") (class "Default")
      (node (ref "PS2") (pin "3") (pinfunction "3_3") (pintype "passive"))
    )
    (net (code "81") (name "unconnected-(PS2-Pad8)") (class "Default")
      (node (ref "PS2") (pin "8") (pinfunction "8_8") (pintype "passive"))
    )
    (net (code "82") (name "unconnected-(PS2-Pad9)") (class "Default")
      (node (ref "PS2") (pin "9") (pinfunction "9_9") (pintype "passive"))
    )
  )
)
